# EAA690_RFID_Outside.net
KiCad netlist of a schematic drawn in EAGLE
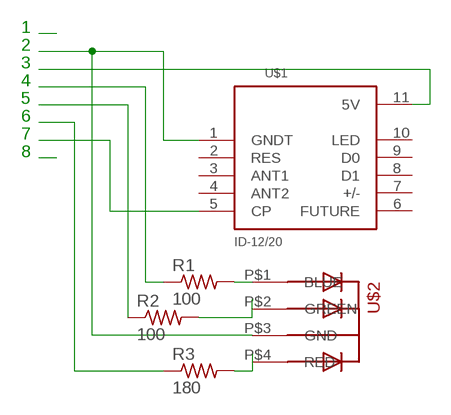
[diagram p0: schematic, sheet 1]

(export (version "E")
  (design (tool "Eeschema 10.0.6"))
  (components
    (comp (ref "R1")
      (value "100")
      (footprint "eagle-import:0204_5")
      (libsource (lib "eagle-import") (part "R-US_0204/5"))
    )
    (comp (ref "R2")
      (value "100")
      (footprint "eagle-import:0204_5")
      (libsource (lib "eagle-import") (part "R-US_0204/5"))
    )
    (comp (ref "R3")
      (value "180")
      (footprint "eagle-import:0204_5")
      (libsource (lib "eagle-import") (part "R-US_0204/5"))
    )
    (comp (ref "U$1")
      (value "ID-12/20")
      (footprint "eagle-import:ID-12")
      (libsource (lib "eagle-import") (part "ID-12/20"))
    )
    (comp (ref "U$2")
      (value "5MMRGBLED")
      (footprint "eagle-import:LED5MMRGB")
      (libsource (lib "eagle-import") (part "5MMRGBLED"))
    )
  )
  (nets
    (net (code "1") (name "Net-(U$1-GNDT)") (class "Default")
      (node (ref "U$1") (pin "1") (pinfunction "GNDT_1") (pintype "bidirectional"))
      (node (ref "U$2") (pin "P$3") (pinfunction "GND_P$3") (pintype "bidirectional"))
    )
    (net (code "2") (name "Net-(U$2-BLUE)") (class "Default")
      (node (ref "R1") (pin "2") (pinfunction "2_2") (pintype "passive"))
      (node (ref "U$2") (pin "P$1") (pinfunction "BLUE_P$1") (pintype "bidirectional"))
    )
    (net (code "3") (name "unconnected-(R1-Pad1)") (class "Default")
      (node (ref "R1") (pin "1") (pinfunction "1_1") (pintype "passive"))
    )
    (net (code "4") (name "unconnected-(R2-Pad1)") (class "Default")
      (node (ref "R2") (pin "1") (pinfunction "1_1") (pintype "passive"))
    )
    (net (code "5") (name "unconnected-(R2-Pad2)") (class "Default")
      (node (ref "R2") (pin "2") (pinfunction "2_2") (pintype "passive"))
    )
    (net (code "6") (name "unconnected-(R3-Pad1)") (class "Default")
      (node (ref "R3") (pin "1") (pinfunction "1_1") (pintype "passive"))
    )
    (net (code "7") (name "unconnected-(R3-Pad2)") (class "Default")
      (node (ref "R3") (pin "2") (pinfunction "2_2") (pintype "passive"))
    )
    (net (code "8") (name "unconnected-(U$1-+{slash}--Pad7)") (class "Default")
      (node (ref "U$1") (pin "7") (pinfunction "+/-_7") (pintype "bidirectional"))
    )
    (net (code "9") (name "unconnected-(U$1-5V-Pad11)") (class "Default")
      (node (ref "U$1") (pin "11") (pinfunction "5V_11") (pintype "bidirectional"))
    )
    (net (code "10") (name "unconnected-(U$1-ANT1-Pad3)") (class "Default")
      (node (ref "U$1") (pin "3") (pinfunction "ANT1_3") (pintype "bidirectional"))
    )
    (net (code "11") (name "unconnected-(U$1-ANT2-Pad4)") (class "Default")
      (node (ref "U$1") (pin "4") (pinfunction "ANT2_4") (pintype "bidirectional"))
    )
    (net (code "12") (name "unconnected-(U$1-CP-Pad5)") (class "Default")
      (node (ref "U$1") (pin "5") (pinfunction "CP_5") (pintype "bidirectional"))
    )
    (net (code "13") (name "unconnected-(U$1-D0-Pad9)") (class "Default")
      (node (ref "U$1") (pin "9") (pinfunction "D0_9") (pintype "bidirectional"))
    )
    (net (code "14") (name "unconnected-(U$1-D1-Pad8)") (class "Default")
      (node (ref "U$1") (pin "8") (pinfunction "D1_8") (pintype "bidirectional"))
    )
    (net (code "15") (name "unconnected-(U$1-FUTURE-Pad6)") (class "Default")
      (node (ref "U$1") (pin "6") (pinfunction "FUTURE_6") (pintype "bidirectional"))
    )
    (net (code "16") (name "unconnected-(U$1-LED-Pad10)") (class "Default")
      (node (ref "U$1") (pin "10") (pinfunction "LED_10") (pintype "bidirectional"))
    )
    (net (code "17") (name "unconnected-(U$1-RES-Pad2)") (class "Default")
      (node (ref "U$1") (pin "2") (pinfunction "RES_2") (pintype "bidirectional"))
    )
    (net (code "18") (name "unconnected-(U$2-GREEN-PadP$2)") (class "Default")
      (node (ref "U$2") (pin "P$2") (pinfunction "GREEN_P$2") (pintype "bidirectional"))
    )
    (net (code "19") (name "unconnected-(U$2-RED-PadP$4)") (class "Default")
      (node (ref "U$2") (pin "P$4") (pinfunction "RED_P$4") (pintype "bidirectional"))
    )
  )
)
